# ESP12_PwmBoard.net
KiCad netlist of a schematic drawn in EAGLE
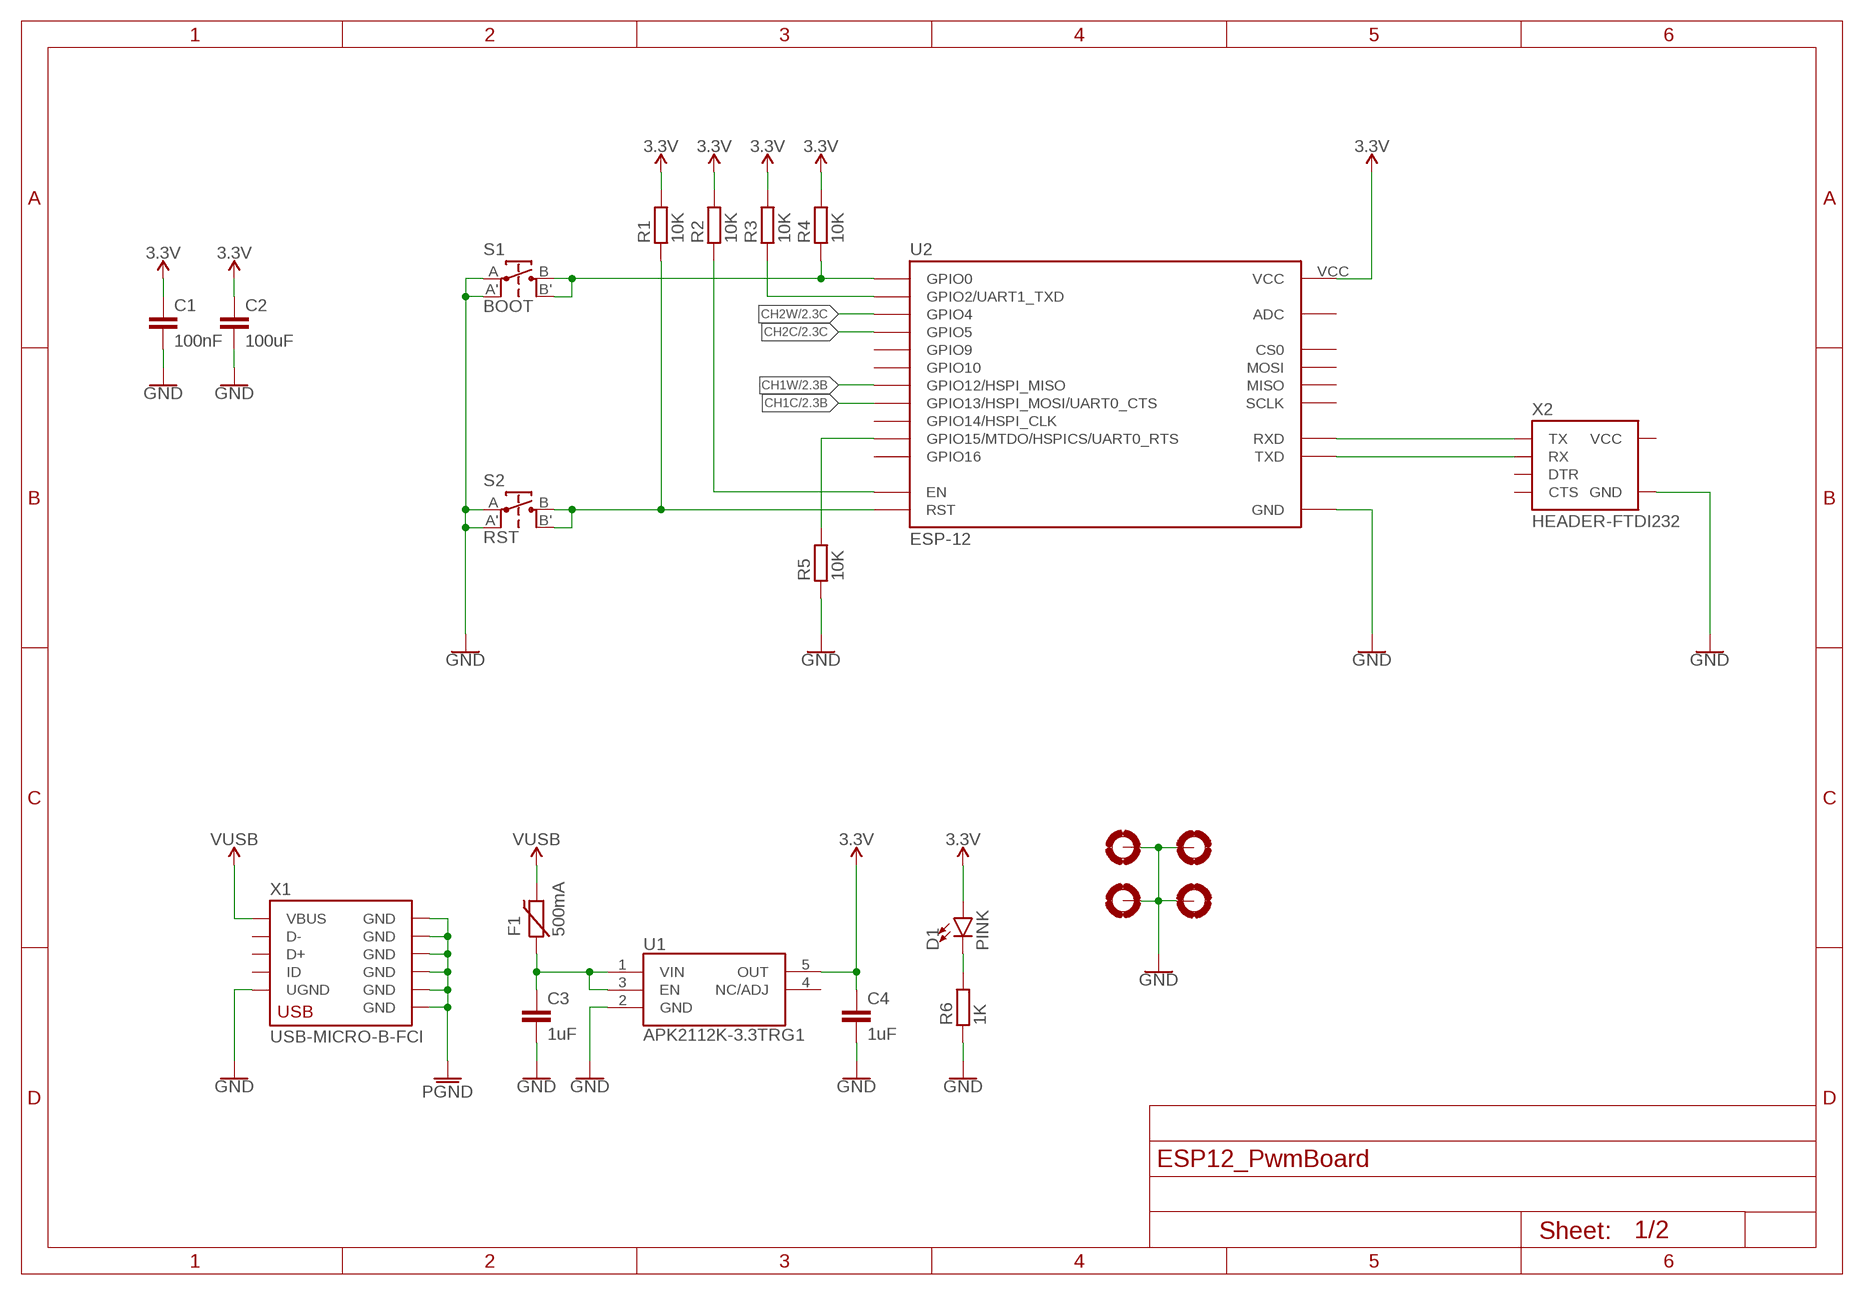
[diagram p0: schematic, sheet 1]
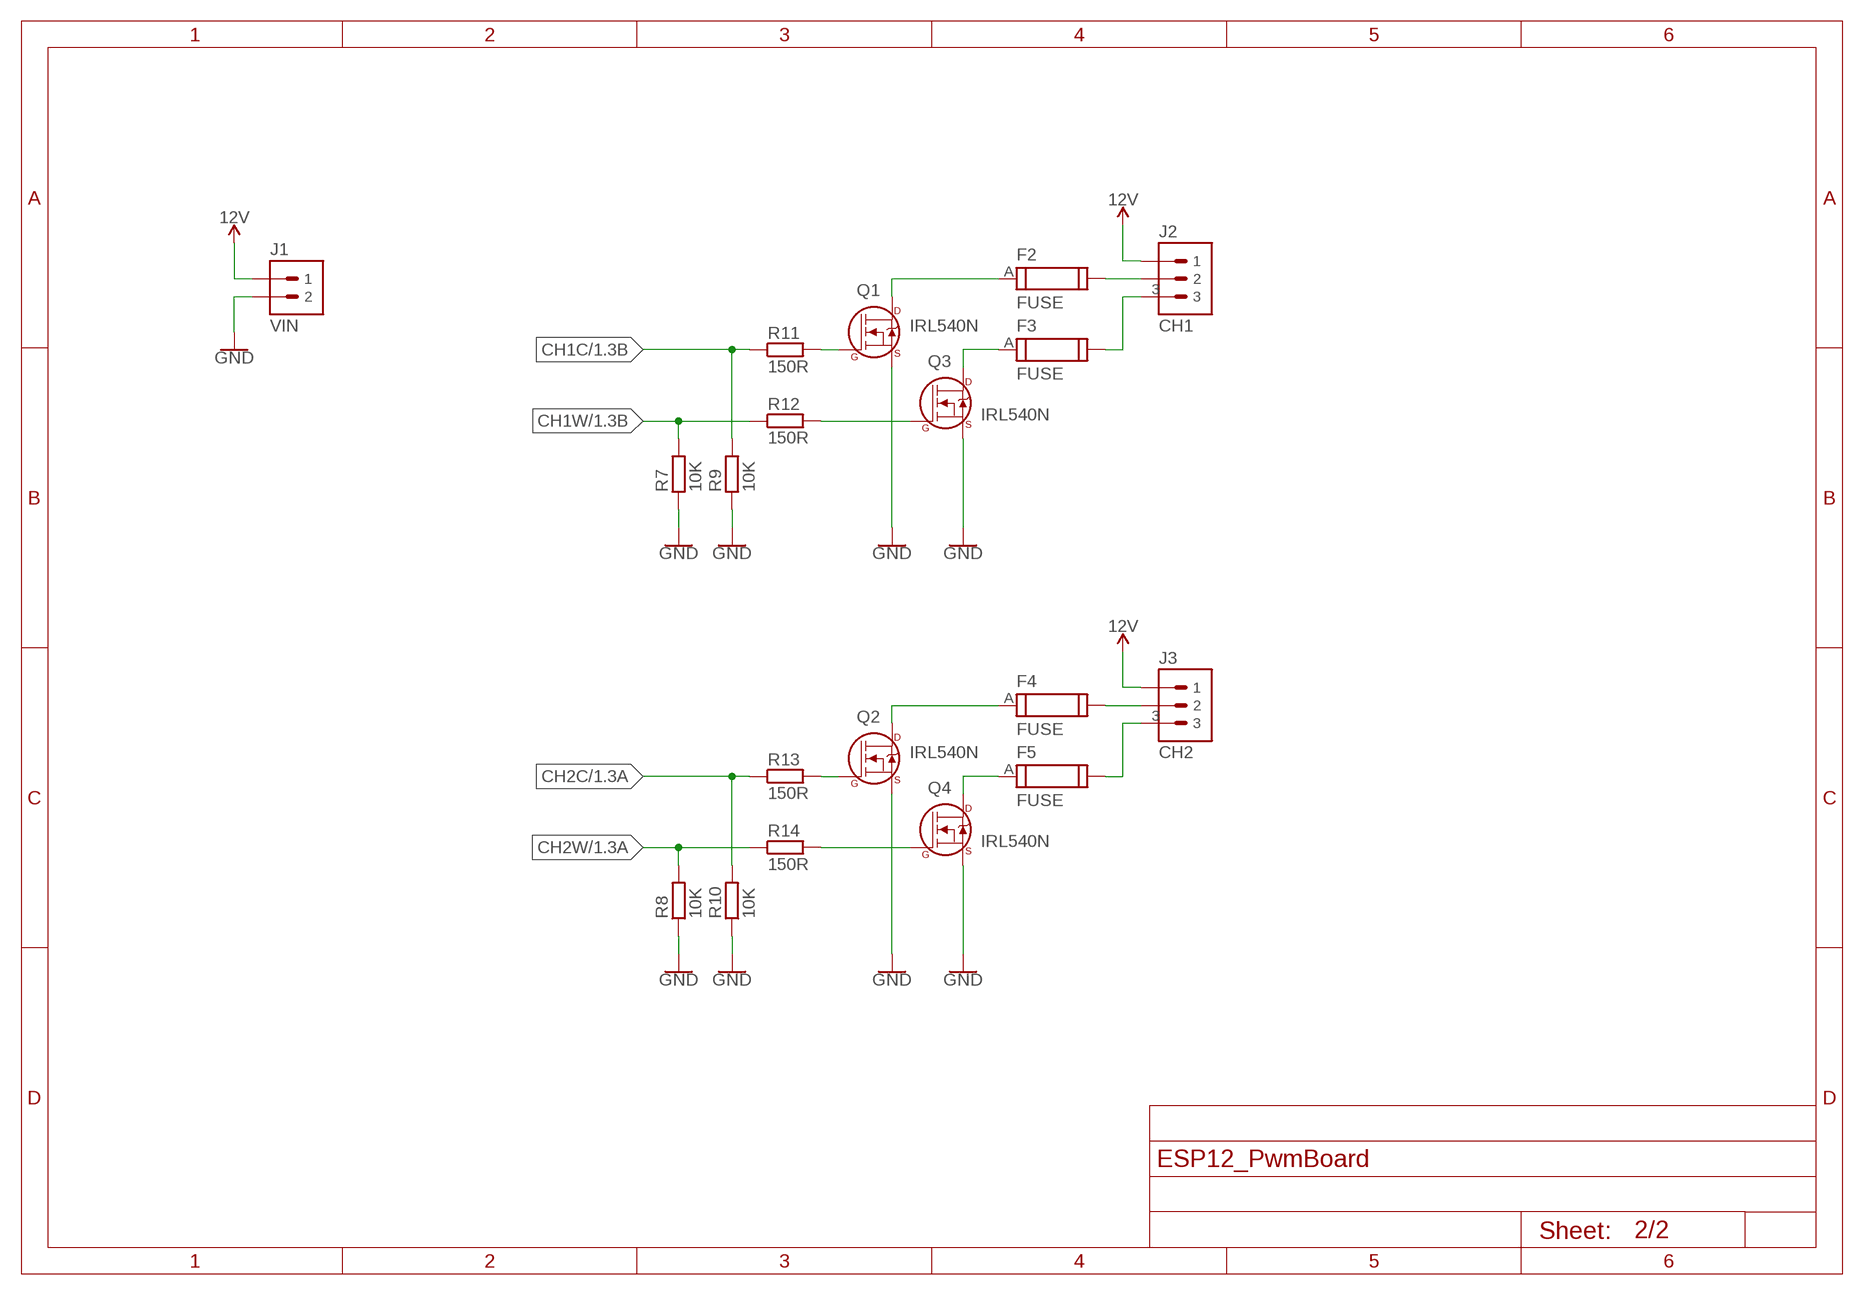
[diagram p1: schematic, sheet 2]

(export (version "E")
  (design (tool "Eeschema 10.0.6"))
  (components
    (comp (ref "C1")
      (value "100nF")
      (footprint "eagle-import:C0603")
      (libsource (lib "eagle-import") (part "CAPC0603"))
    )
    (comp (ref "C2")
      (value "100uF")
      (footprint "eagle-import:C0603")
      (libsource (lib "eagle-import") (part "CAPC0603"))
    )
    (comp (ref "C3")
      (value "1uF")
      (footprint "eagle-import:C0603")
      (libsource (lib "eagle-import") (part "CAPC0603"))
    )
    (comp (ref "C4")
      (value "1uF")
      (footprint "eagle-import:C0603")
      (libsource (lib "eagle-import") (part "CAPC0603"))
    )
    (comp (ref "D1")
      (value "PINK")
      (footprint "eagle-import:LED0603")
      (libsource (lib "eagle-import") (part "LED0603"))
    )
    (comp (ref "F1")
      (value "500mA")
      (footprint "eagle-import:PTC-0ZCJ-1206")
      (libsource (lib "eagle-import") (part "PTC0ZCJ"))
    )
    (comp (ref "H1")
      (value "MOUNTHOLE-PAD3.2")
      (footprint "eagle-import:3.2-PAD")
      (libsource (lib "eagle-import") (part "MOUNTHOLE-PAD3.2"))
    )
    (comp (ref "H2")
      (value "MOUNTHOLE-PAD3.2")
      (footprint "eagle-import:3.2-PAD")
      (libsource (lib "eagle-import") (part "MOUNTHOLE-PAD3.2"))
    )
    (comp (ref "H3")
      (value "MOUNTHOLE-PAD3.2")
      (footprint "eagle-import:3.2-PAD")
      (libsource (lib "eagle-import") (part "MOUNTHOLE-PAD3.2"))
    )
    (comp (ref "H4")
      (value "MOUNTHOLE-PAD3.2")
      (footprint "eagle-import:3.2-PAD")
      (libsource (lib "eagle-import") (part "MOUNTHOLE-PAD3.2"))
    )
    (comp (ref "R1")
      (value "10K")
      (footprint "eagle-import:R0603")
      (libsource (lib "eagle-import") (part "RESISTOR0603"))
    )
    (comp (ref "R2")
      (value "10K")
      (footprint "eagle-import:R0603")
      (libsource (lib "eagle-import") (part "RESISTOR0603"))
    )
    (comp (ref "R3")
      (value "10K")
      (footprint "eagle-import:R0603")
      (libsource (lib "eagle-import") (part "RESISTOR0603"))
    )
    (comp (ref "R4")
      (value "10K")
      (footprint "eagle-import:R0603")
      (libsource (lib "eagle-import") (part "RESISTOR0603"))
    )
    (comp (ref "R5")
      (value "10K")
      (footprint "eagle-import:R0603")
      (libsource (lib "eagle-import") (part "RESISTOR0603"))
    )
    (comp (ref "R6")
      (value "1K")
      (footprint "eagle-import:R0603")
      (libsource (lib "eagle-import") (part "RESISTOR0603"))
    )
    (comp (ref "S1")
      (value "BOOT")
      (footprint "eagle-import:TACT-SWITCH-EVQ")
      (libsource (lib "eagle-import") (part "TACT-SWITCH-EVQEVQ-Q2Y03W"))
    )
    (comp (ref "S2")
      (value "RST")
      (footprint "eagle-import:TACT-SWITCH-EVQ")
      (libsource (lib "eagle-import") (part "TACT-SWITCH-EVQEVQ-Q2Y03W"))
    )
    (comp (ref "U1")
      (value "APK2112K-3.3TRG1")
      (footprint "eagle-import:SOT23-5")
      (libsource (lib "eagle-import") (part "REGULATOR-AP2112KK-SOT23-5"))
    )
    (comp (ref "U2")
      (value "ESP-12")
      (footprint "eagle-import:ESP-12E")
      (libsource (lib "eagle-import") (part "ESP-12E"))
    )
    (comp (ref "X1")
      (value "USB-MICRO-B-FCI")
      (footprint "eagle-import:USB-MICRO-B-FCI")
      (libsource (lib "eagle-import") (part "USB-MICRO-B-FCI"))
    )
    (comp (ref "X2")
      (value "HEADER-FTDI232")
      (footprint "eagle-import:FTDI232-1X06")
      (libsource (lib "eagle-import") (part "HEADER-FTDI232"))
    )
    (comp (ref "F2")
      (value "FUSE")
      (footprint "eagle-import:FUSE-TEAL")
      (libsource (lib "eagle-import") (part "FUSETEAL"))
    )
    (comp (ref "F3")
      (value "FUSE")
      (footprint "eagle-import:FUSE-TEAL")
      (libsource (lib "eagle-import") (part "FUSETEAL"))
    )
    (comp (ref "F4")
      (value "FUSE")
      (footprint "eagle-import:FUSE-TEAL")
      (libsource (lib "eagle-import") (part "FUSETEAL"))
    )
    (comp (ref "F5")
      (value "FUSE")
      (footprint "eagle-import:FUSE-TEAL")
      (libsource (lib "eagle-import") (part "FUSETEAL"))
    )
    (comp (ref "J1")
      (value "VIN")
      (footprint "eagle-import:ONSHORE-OSTTC022162")
      (libsource (lib "eagle-import") (part "TERMINAL-1X02-5.08OSTTC022162"))
    )
    (comp (ref "J2")
      (value "CH1")
      (footprint "eagle-import:ONSHORE-OSTTC032162")
      (libsource (lib "eagle-import") (part "TERMINAL-1X03-5.08OSTTC032162"))
    )
    (comp (ref "J3")
      (value "CH2")
      (footprint "eagle-import:ONSHORE-OSTTC032162")
      (libsource (lib "eagle-import") (part "TERMINAL-1X03-5.08OSTTC032162"))
    )
    (comp (ref "Q1")
      (value "IRL540N")
      (footprint "eagle-import:TO-220AB")
      (libsource (lib "eagle-import") (part "MOSFET-NCHTO-220AB"))
    )
    (comp (ref "Q2")
      (value "IRL540N")
      (footprint "eagle-import:TO-220AB")
      (libsource (lib "eagle-import") (part "MOSFET-NCHTO-220AB"))
    )
    (comp (ref "Q3")
      (value "IRL540N")
      (footprint "eagle-import:TO-220AB")
      (libsource (lib "eagle-import") (part "MOSFET-NCHTO-220AB"))
    )
    (comp (ref "Q4")
      (value "IRL540N")
      (footprint "eagle-import:TO-220AB")
      (libsource (lib "eagle-import") (part "MOSFET-NCHTO-220AB"))
    )
    (comp (ref "R7")
      (value "10K")
      (footprint "eagle-import:R0603")
      (libsource (lib "eagle-import") (part "RESISTOR0603"))
    )
    (comp (ref "R8")
      (value "10K")
      (footprint "eagle-import:R0603")
      (libsource (lib "eagle-import") (part "RESISTOR0603"))
    )
    (comp (ref "R9")
      (value "10K")
      (footprint "eagle-import:R0603")
      (libsource (lib "eagle-import") (part "RESISTOR0603"))
    )
    (comp (ref "R10")
      (value "10K")
      (footprint "eagle-import:R0603")
      (libsource (lib "eagle-import") (part "RESISTOR0603"))
    )
    (comp (ref "R11")
      (value "150R")
      (footprint "eagle-import:R0603")
      (libsource (lib "eagle-import") (part "RESISTOR0603"))
    )
    (comp (ref "R12")
      (value "150R")
      (footprint "eagle-import:R0603")
      (libsource (lib "eagle-import") (part "RESISTOR0603"))
    )
    (comp (ref "R13")
      (value "150R")
      (footprint "eagle-import:R0603")
      (libsource (lib "eagle-import") (part "RESISTOR0603"))
    )
    (comp (ref "R14")
      (value "150R")
      (footprint "eagle-import:R0603")
      (libsource (lib "eagle-import") (part "RESISTOR0603"))
    )
  )
  (nets
    (net (code "1") (name "3.3V") (class "Default")
      (node (ref "C1") (pin "1") (pinfunction "1_1") (pintype "passive"))
      (node (ref "C2") (pin "1") (pinfunction "1_1") (pintype "passive"))
      (node (ref "C4") (pin "1") (pinfunction "1_1") (pintype "passive"))
      (node (ref "D1") (pin "A") (pinfunction "A_A") (pintype "passive"))
      (node (ref "R1") (pin "2") (pinfunction "2_2") (pintype "passive"))
      (node (ref "R2") (pin "2") (pinfunction "2_2") (pintype "passive"))
      (node (ref "R3") (pin "2") (pinfunction "2_2") (pintype "passive"))
      (node (ref "R4") (pin "2") (pinfunction "2_2") (pintype "passive"))
      (node (ref "U1") (pin "5") (pinfunction "OUT_5") (pintype "power_in"))
      (node (ref "U2") (pin "VCC") (pinfunction "VCC_VCC") (pintype "bidirectional"))
    )
    (net (code "2") (name "12V") (class "Default")
      (node (ref "J1") (pin "1") (pinfunction "1_1") (pintype "passive"))
      (node (ref "J2") (pin "1") (pinfunction "1_1") (pintype "passive"))
      (node (ref "J3") (pin "1") (pinfunction "1_1") (pintype "passive"))
    )
    (net (code "3") (name "CH1C") (class "Default")
      (node (ref "R11") (pin "1") (pinfunction "1_1") (pintype "passive"))
      (node (ref "R9") (pin "2") (pinfunction "2_2") (pintype "passive"))
      (node (ref "U2") (pin "GPIO13") (pinfunction "GPIO13/HSPI_MOSI/UART0_CTS_GPIO13") (pintype "bidirectional"))
    )
    (net (code "4") (name "CH1W") (class "Default")
      (node (ref "R12") (pin "1") (pinfunction "1_1") (pintype "passive"))
      (node (ref "R7") (pin "2") (pinfunction "2_2") (pintype "passive"))
      (node (ref "U2") (pin "GPIO12") (pinfunction "GPIO12/HSPI_MISO_GPIO12") (pintype "bidirectional"))
    )
    (net (code "5") (name "CH2C") (class "Default")
      (node (ref "R10") (pin "2") (pinfunction "2_2") (pintype "passive"))
      (node (ref "R13") (pin "1") (pinfunction "1_1") (pintype "passive"))
      (node (ref "U2") (pin "GPIO5") (pinfunction "GPIO5_GPIO5") (pintype "bidirectional"))
    )
    (net (code "6") (name "CH2W") (class "Default")
      (node (ref "R14") (pin "1") (pinfunction "1_1") (pintype "passive"))
      (node (ref "R8") (pin "2") (pinfunction "2_2") (pintype "passive"))
      (node (ref "U2") (pin "GPIO4") (pinfunction "GPIO4_GPIO4") (pintype "bidirectional"))
    )
    (net (code "7") (name "GND") (class "Default")
      (node (ref "C1") (pin "2") (pinfunction "2_2") (pintype "passive"))
      (node (ref "C2") (pin "2") (pinfunction "2_2") (pintype "passive"))
      (node (ref "C3") (pin "2") (pinfunction "2_2") (pintype "passive"))
      (node (ref "C4") (pin "2") (pinfunction "2_2") (pintype "passive"))
      (node (ref "H1") (pin "B3,2") (pinfunction "MOUNT_B3,2") (pintype "passive"))
      (node (ref "H2") (pin "B3,2") (pinfunction "MOUNT_B3,2") (pintype "passive"))
      (node (ref "H3") (pin "B3,2") (pinfunction "MOUNT_B3,2") (pintype "passive"))
      (node (ref "H4") (pin "B3,2") (pinfunction "MOUNT_B3,2") (pintype "passive"))
      (node (ref "J1") (pin "2") (pinfunction "2_2") (pintype "passive"))
      (node (ref "Q1") (pin "3") (pinfunction "S_3") (pintype "bidirectional"))
      (node (ref "Q2") (pin "3") (pinfunction "S_3") (pintype "bidirectional"))
      (node (ref "Q3") (pin "3") (pinfunction "S_3") (pintype "bidirectional"))
      (node (ref "Q4") (pin "3") (pinfunction "S_3") (pintype "bidirectional"))
      (node (ref "R10") (pin "1") (pinfunction "1_1") (pintype "passive"))
      (node (ref "R5") (pin "1") (pinfunction "1_1") (pintype "passive"))
      (node (ref "R6") (pin "1") (pinfunction "1_1") (pintype "passive"))
      (node (ref "R7") (pin "1") (pinfunction "1_1") (pintype "passive"))
      (node (ref "R8") (pin "1") (pinfunction "1_1") (pintype "passive"))
      (node (ref "R9") (pin "1") (pinfunction "1_1") (pintype "passive"))
      (node (ref "S1") (pin "A") (pinfunction "A_A") (pintype "bidirectional"))
      (node (ref "S1") (pin "A'") (pinfunction "A'_A'") (pintype "bidirectional"))
      (node (ref "S2") (pin "A") (pinfunction "A_A") (pintype "bidirectional"))
      (node (ref "S2") (pin "A'") (pinfunction "A'_A'") (pintype "bidirectional"))
      (node (ref "U1") (pin "2") (pinfunction "GND_2") (pintype "power_in"))
      (node (ref "U2") (pin "GND") (pinfunction "GND_GND") (pintype "bidirectional"))
      (node (ref "X1") (pin "5") (pinfunction "UGND_5") (pintype "power_in"))
      (node (ref "X2") (pin "GND") (pinfunction "GND_GND") (pintype "power_in"))
    )
    (net (code "8") (name "Net-(D1-PadC)") (class "Default")
      (node (ref "D1") (pin "C") (pinfunction "C_C") (pintype "passive"))
      (node (ref "R6") (pin "2") (pinfunction "2_2") (pintype "passive"))
    )
    (net (code "9") (name "Net-(F2-PadB)") (class "Default")
      (node (ref "F2") (pin "B") (pinfunction "B_B") (pintype "bidirectional"))
      (node (ref "J2") (pin "2") (pinfunction "2_2") (pintype "passive"))
    )
    (net (code "10") (name "Net-(F3-PadB)") (class "Default")
      (node (ref "F3") (pin "B") (pinfunction "B_B") (pintype "bidirectional"))
      (node (ref "J2") (pin "3") (pinfunction "3_3") (pintype "passive"))
    )
    (net (code "11") (name "Net-(F4-PadB)") (class "Default")
      (node (ref "F4") (pin "B") (pinfunction "B_B") (pintype "bidirectional"))
      (node (ref "J3") (pin "2") (pinfunction "2_2") (pintype "passive"))
    )
    (net (code "12") (name "Net-(F5-PadB)") (class "Default")
      (node (ref "F5") (pin "B") (pinfunction "B_B") (pintype "bidirectional"))
      (node (ref "J3") (pin "3") (pinfunction "3_3") (pintype "passive"))
    )
    (net (code "13") (name "Net-(Q1-D)") (class "Default")
      (node (ref "F2") (pin "A") (pinfunction "A_A") (pintype "bidirectional"))
      (node (ref "Q1") (pin "2") (pinfunction "D_2") (pintype "bidirectional"))
    )
    (net (code "14") (name "Net-(Q1-G)") (class "Default")
      (node (ref "Q1") (pin "1") (pinfunction "G_1") (pintype "bidirectional"))
      (node (ref "R11") (pin "2") (pinfunction "2_2") (pintype "passive"))
    )
    (net (code "15") (name "Net-(Q2-D)") (class "Default")
      (node (ref "F4") (pin "A") (pinfunction "A_A") (pintype "bidirectional"))
      (node (ref "Q2") (pin "2") (pinfunction "D_2") (pintype "bidirectional"))
    )
    (net (code "16") (name "Net-(Q2-G)") (class "Default")
      (node (ref "Q2") (pin "1") (pinfunction "G_1") (pintype "bidirectional"))
      (node (ref "R13") (pin "2") (pinfunction "2_2") (pintype "passive"))
    )
    (net (code "17") (name "Net-(Q3-D)") (class "Default")
      (node (ref "F3") (pin "A") (pinfunction "A_A") (pintype "bidirectional"))
      (node (ref "Q3") (pin "2") (pinfunction "D_2") (pintype "bidirectional"))
    )
    (net (code "18") (name "Net-(Q3-G)") (class "Default")
      (node (ref "Q3") (pin "1") (pinfunction "G_1") (pintype "bidirectional"))
      (node (ref "R12") (pin "2") (pinfunction "2_2") (pintype "passive"))
    )
    (net (code "19") (name "Net-(Q4-D)") (class "Default")
      (node (ref "F5") (pin "A") (pinfunction "A_A") (pintype "bidirectional"))
      (node (ref "Q4") (pin "2") (pinfunction "D_2") (pintype "bidirectional"))
    )
    (net (code "20") (name "Net-(Q4-G)") (class "Default")
      (node (ref "Q4") (pin "1") (pinfunction "G_1") (pintype "bidirectional"))
      (node (ref "R14") (pin "2") (pinfunction "2_2") (pintype "passive"))
    )
    (net (code "21") (name "Net-(R1-Pad1)") (class "Default")
      (node (ref "R1") (pin "1") (pinfunction "1_1") (pintype "passive"))
      (node (ref "S2") (pin "B") (pinfunction "B_B") (pintype "bidirectional"))
      (node (ref "S2") (pin "B'") (pinfunction "B'_B'") (pintype "bidirectional"))
      (node (ref "U2") (pin "RST") (pinfunction "RST_RST") (pintype "bidirectional"))
    )
    (net (code "22") (name "Net-(R2-Pad1)") (class "Default")
      (node (ref "R2") (pin "1") (pinfunction "1_1") (pintype "passive"))
      (node (ref "U2") (pin "EN") (pinfunction "EN_EN") (pintype "bidirectional"))
    )
    (net (code "23") (name "Net-(R4-Pad1)") (class "Default")
      (node (ref "R4") (pin "1") (pinfunction "1_1") (pintype "passive"))
      (node (ref "S1") (pin "B") (pinfunction "B_B") (pintype "bidirectional"))
      (node (ref "S1") (pin "B'") (pinfunction "B'_B'") (pintype "bidirectional"))
      (node (ref "U2") (pin "GPIO0") (pinfunction "GPIO0_GPIO0") (pintype "bidirectional"))
    )
    (net (code "24") (name "Net-(U1-EN)") (class "Default")
      (node (ref "C3") (pin "1") (pinfunction "1_1") (pintype "passive"))
      (node (ref "F1") (pin "1") (pinfunction "1_1") (pintype "bidirectional"))
      (node (ref "U1") (pin "1") (pinfunction "VIN_1") (pintype "power_in"))
      (node (ref "U1") (pin "3") (pinfunction "EN_3") (pintype "input"))
    )
    (net (code "25") (name "Net-(U2-GPIO2{slash}UART1_TXD)") (class "Default")
      (node (ref "R3") (pin "1") (pinfunction "1_1") (pintype "passive"))
      (node (ref "U2") (pin "GPIO2") (pinfunction "GPIO2/UART1_TXD_GPIO2") (pintype "bidirectional"))
    )
    (net (code "26") (name "Net-(U2-GPIO15{slash}MTDO{slash}HSPICS{slash}UART0_RTS)") (class "Default")
      (node (ref "R5") (pin "2") (pinfunction "2_2") (pintype "passive"))
      (node (ref "U2") (pin "GPIO15") (pinfunction "GPIO15/MTDO/HSPICS/UART0_RTS_GPIO15") (pintype "bidirectional"))
    )
    (net (code "27") (name "Net-(U2-PadRXD)") (class "Default")
      (node (ref "U2") (pin "RXD") (pinfunction "RXD_RXD") (pintype "bidirectional"))
      (node (ref "X2") (pin "TX") (pinfunction "TX_TX") (pintype "output"))
    )
    (net (code "28") (name "Net-(U2-PadTXD)") (class "Default")
      (node (ref "U2") (pin "TXD") (pinfunction "TXD_TXD") (pintype "bidirectional"))
      (node (ref "X2") (pin "RX") (pinfunction "RX_RX") (pintype "input"))
    )
    (net (code "29") (name "PGND") (class "Default")
      (node (ref "X1") (pin "GND@1") (pinfunction "GND_GND@1") (pintype "power_in"))
      (node (ref "X1") (pin "GND@2") (pinfunction "GND_GND@2") (pintype "power_in"))
      (node (ref "X1") (pin "GND@3") (pinfunction "GND_GND@3") (pintype "power_in"))
      (node (ref "X1") (pin "GND@4") (pinfunction "GND_GND@4") (pintype "power_in"))
      (node (ref "X1") (pin "GND@5") (pinfunction "GND_GND@5") (pintype "power_in"))
      (node (ref "X1") (pin "GND@6") (pinfunction "GND_GND@6") (pintype "power_in"))
    )
    (net (code "30") (name "VCC") (class "Default")
      (node (ref "X2") (pin "VCC") (pinfunction "VCC_VCC") (pintype "power_in"))
    )
    (net (code "31") (name "VUSB") (class "Default")
      (node (ref "F1") (pin "2") (pinfunction "2_2") (pintype "bidirectional"))
      (node (ref "X1") (pin "1") (pinfunction "VBUS_1") (pintype "power_in"))
    )
    (net (code "32") (name "unconnected-(U1-NC{slash}ADJ-Pad4)") (class "Default")
      (node (ref "U1") (pin "4") (pinfunction "NC/ADJ_4") (pintype "passive"))
    )
    (net (code "33") (name "unconnected-(U2-GPIO14{slash}HSPI_CLK-PadGPIO14)") (class "Default")
      (node (ref "U2") (pin "GPIO14") (pinfunction "GPIO14/HSPI_CLK_GPIO14") (pintype "bidirectional"))
    )
    (net (code "34") (name "unconnected-(U2-PadADC)") (class "Default")
      (node (ref "U2") (pin "ADC") (pinfunction "ADC_ADC") (pintype "bidirectional"))
    )
    (net (code "35") (name "unconnected-(U2-PadCS0)") (class "Default")
      (node (ref "U2") (pin "CS0") (pinfunction "CS0_CS0") (pintype "bidirectional"))
    )
    (net (code "36") (name "unconnected-(U2-PadGPIO9)") (class "Default")
      (node (ref "U2") (pin "GPIO9") (pinfunction "GPIO9_GPIO9") (pintype "bidirectional"))
    )
    (net (code "37") (name "unconnected-(U2-PadGPIO10)") (class "Default")
      (node (ref "U2") (pin "GPIO10") (pinfunction "GPIO10_GPIO10") (pintype "bidirectional"))
    )
    (net (code "38") (name "unconnected-(U2-PadGPIO16)") (class "Default")
      (node (ref "U2") (pin "GPIO16") (pinfunction "GPIO16_GPIO16") (pintype "bidirectional"))
    )
    (net (code "39") (name "unconnected-(U2-PadMISO)") (class "Default")
      (node (ref "U2") (pin "MISO") (pinfunction "MISO_MISO") (pintype "bidirectional"))
    )
    (net (code "40") (name "unconnected-(U2-PadMOSI)") (class "Default")
      (node (ref "U2") (pin "MOSI") (pinfunction "MOSI_MOSI") (pintype "bidirectional"))
    )
    (net (code "41") (name "unconnected-(U2-PadSCLK)") (class "Default")
      (node (ref "U2") (pin "SCLK") (pinfunction "SCLK_SCLK") (pintype "bidirectional"))
    )
    (net (code "42") (name "unconnected-(X1-D+-Pad3)") (class "Default")
      (node (ref "X1") (pin "3") (pinfunction "D+_3") (pintype "bidirectional"))
    )
    (net (code "43") (name "unconnected-(X1-D--Pad2)") (class "Default")
      (node (ref "X1") (pin "2") (pinfunction "D-_2") (pintype "bidirectional"))
    )
    (net (code "44") (name "unconnected-(X1-ID-Pad4)") (class "Default")
      (node (ref "X1") (pin "4") (pinfunction "ID_4") (pintype "bidirectional"))
    )
    (net (code "45") (name "unconnected-(X2-PadCTS)") (class "Default")
      (node (ref "X2") (pin "CTS") (pinfunction "CTS_CTS") (pintype "output"))
    )
    (net (code "46") (name "unconnected-(X2-PadDTR)") (class "Default")
      (node (ref "X2") (pin "DTR") (pinfunction "DTR_DTR") (pintype "output"))
    )
  )
)
